# trunsmeetur.net
KiCad netlist of a schematic drawn in EAGLE
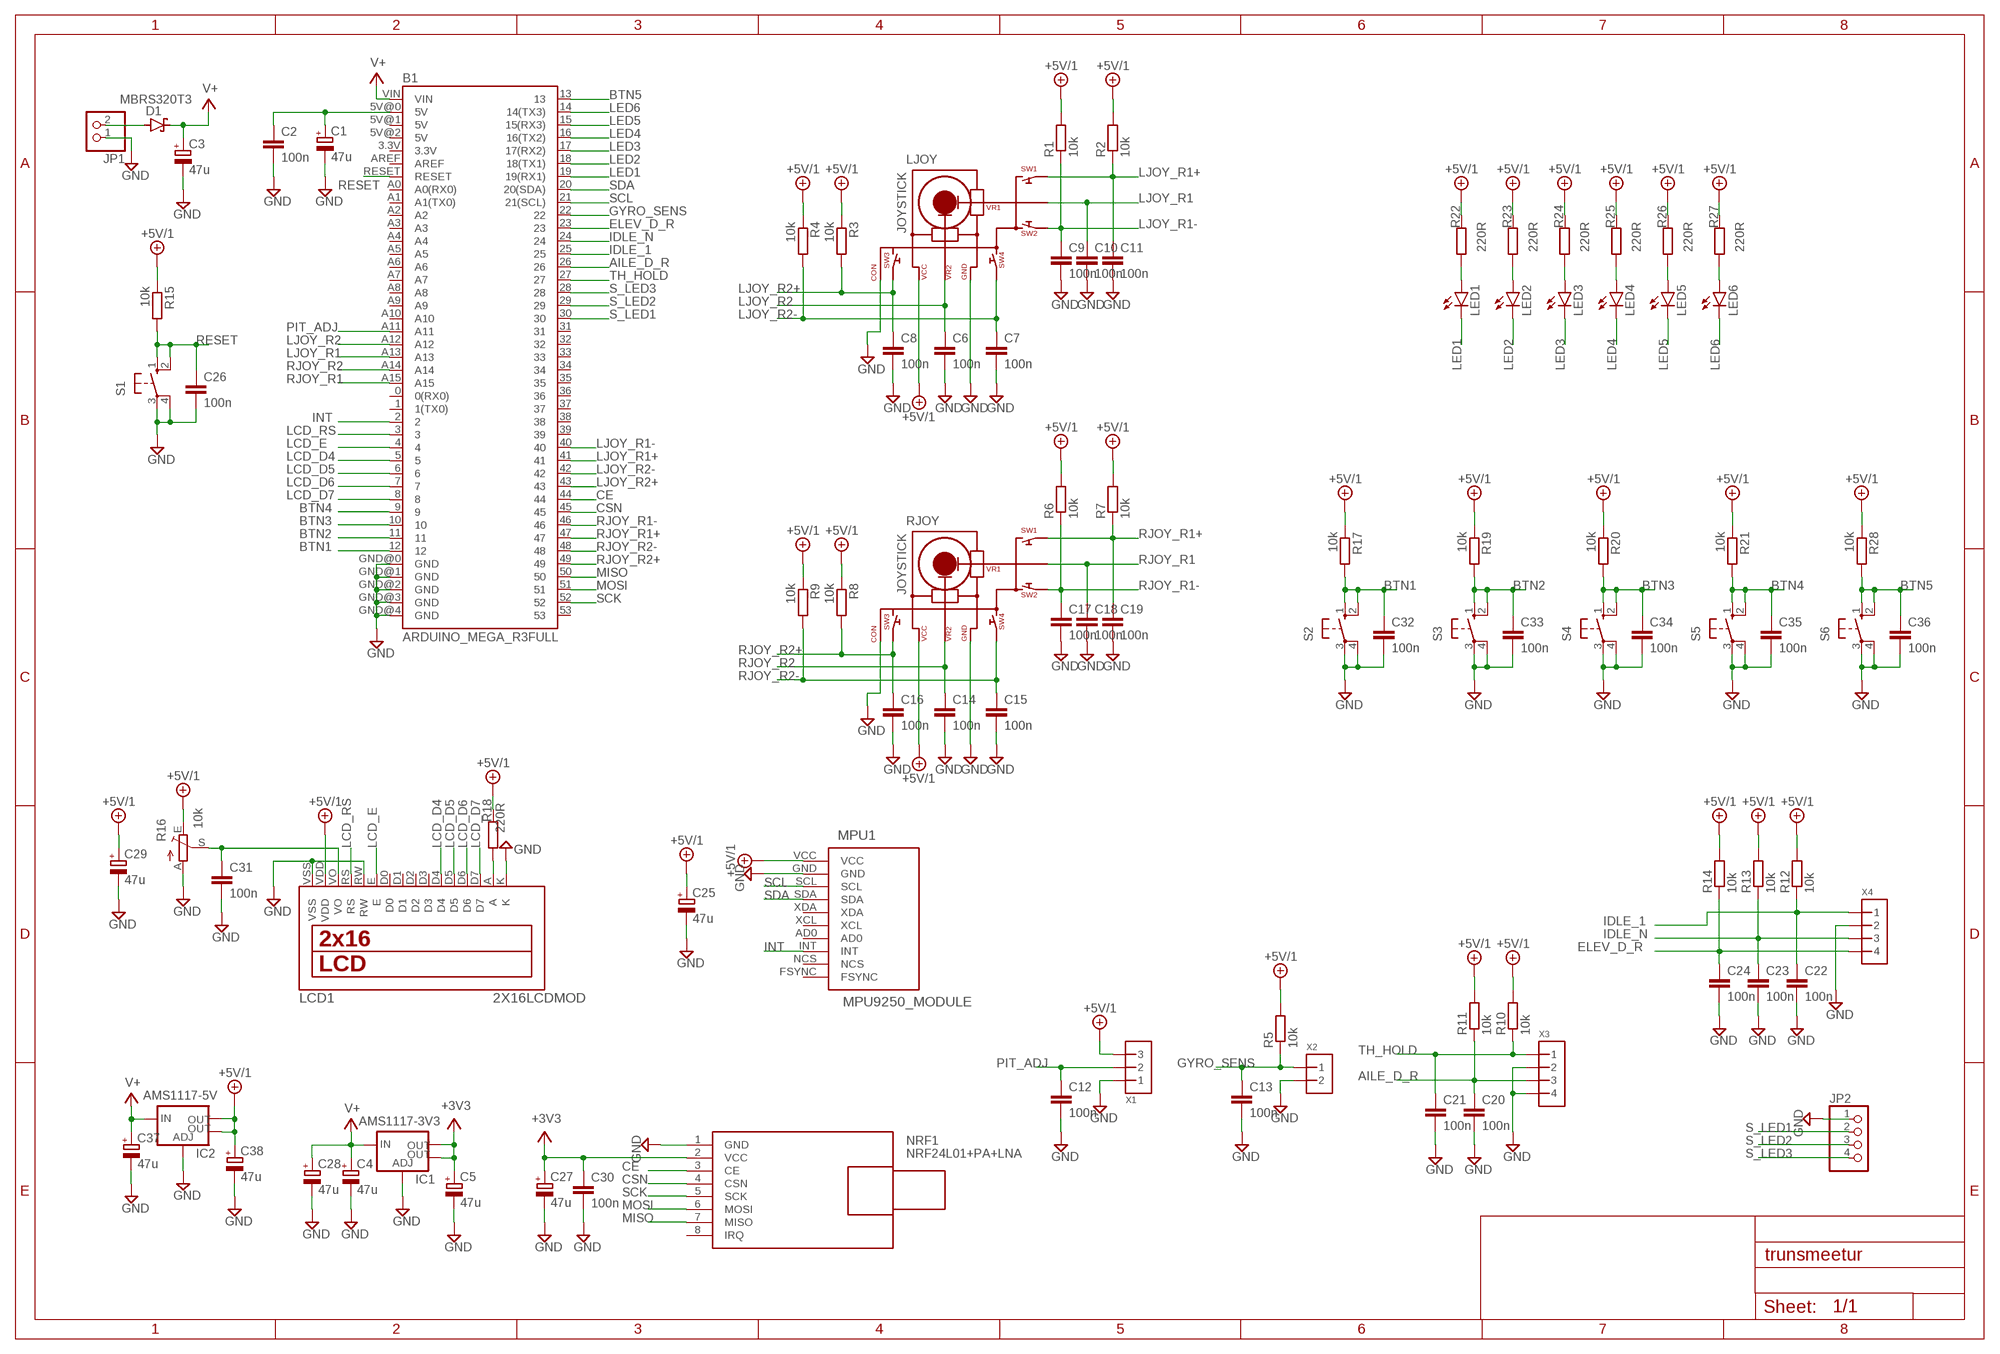
[diagram p0: schematic, sheet 1]

(export (version "E")
  (design (tool "Eeschema 10.0.6"))
  (components
    (comp (ref "B1")
      (value "ARDUINO_MEGA_R3FULL")
      (footprint "eagle-import:ARDUINO_MEGA")
      (libsource (lib "eagle-import") (part "ARDUINO_MEGA_R3FULL"))
    )
    (comp (ref "C1")
      (value "47u")
      (footprint "eagle-import:153CLV-0605")
      (libsource (lib "eagle-import") (part "CPOL-EU153CLV-0605"))
    )
    (comp (ref "C2")
      (value "100n")
      (footprint "eagle-import:C0805")
      (libsource (lib "eagle-import") (part "C-EUC0805"))
    )
    (comp (ref "C3")
      (value "47u")
      (footprint "eagle-import:153CLV-0605")
      (libsource (lib "eagle-import") (part "CPOL-EU153CLV-0605"))
    )
    (comp (ref "C4")
      (value "47u")
      (footprint "eagle-import:153CLV-0605")
      (libsource (lib "eagle-import") (part "CPOL-EU153CLV-0605"))
    )
    (comp (ref "C5")
      (value "47u")
      (footprint "eagle-import:153CLV-0605")
      (libsource (lib "eagle-import") (part "CPOL-EU153CLV-0605"))
    )
    (comp (ref "C6")
      (value "100n")
      (footprint "eagle-import:C0805")
      (libsource (lib "eagle-import") (part "C-EUC0805"))
    )
    (comp (ref "C7")
      (value "100n")
      (footprint "eagle-import:C0805")
      (libsource (lib "eagle-import") (part "C-EUC0805"))
    )
    (comp (ref "C8")
      (value "100n")
      (footprint "eagle-import:C0805")
      (libsource (lib "eagle-import") (part "C-EUC0805"))
    )
    (comp (ref "C9")
      (value "100n")
      (footprint "eagle-import:C0805")
      (libsource (lib "eagle-import") (part "C-EUC0805"))
    )
    (comp (ref "C10")
      (value "100n")
      (footprint "eagle-import:C0805")
      (libsource (lib "eagle-import") (part "C-EUC0805"))
    )
    (comp (ref "C11")
      (value "100n")
      (footprint "eagle-import:C0805")
      (libsource (lib "eagle-import") (part "C-EUC0805"))
    )
    (comp (ref "C12")
      (value "100n")
      (footprint "eagle-import:C0805")
      (libsource (lib "eagle-import") (part "C-EUC0805"))
    )
    (comp (ref "C13")
      (value "100n")
      (footprint "eagle-import:C0805")
      (libsource (lib "eagle-import") (part "C-EUC0805"))
    )
    (comp (ref "C14")
      (value "100n")
      (footprint "eagle-import:C0805")
      (libsource (lib "eagle-import") (part "C-EUC0805"))
    )
    (comp (ref "C15")
      (value "100n")
      (footprint "eagle-import:C0805")
      (libsource (lib "eagle-import") (part "C-EUC0805"))
    )
    (comp (ref "C16")
      (value "100n")
      (footprint "eagle-import:C0805")
      (libsource (lib "eagle-import") (part "C-EUC0805"))
    )
    (comp (ref "C17")
      (value "100n")
      (footprint "eagle-import:C0805")
      (libsource (lib "eagle-import") (part "C-EUC0805"))
    )
    (comp (ref "C18")
      (value "100n")
      (footprint "eagle-import:C0805")
      (libsource (lib "eagle-import") (part "C-EUC0805"))
    )
    (comp (ref "C19")
      (value "100n")
      (footprint "eagle-import:C0805")
      (libsource (lib "eagle-import") (part "C-EUC0805"))
    )
    (comp (ref "C20")
      (value "100n")
      (footprint "eagle-import:C0805")
      (libsource (lib "eagle-import") (part "C-EUC0805"))
    )
    (comp (ref "C21")
      (value "100n")
      (footprint "eagle-import:C0805")
      (libsource (lib "eagle-import") (part "C-EUC0805"))
    )
    (comp (ref "C22")
      (value "100n")
      (footprint "eagle-import:C0805")
      (libsource (lib "eagle-import") (part "C-EUC0805"))
    )
    (comp (ref "C23")
      (value "100n")
      (footprint "eagle-import:C0805")
      (libsource (lib "eagle-import") (part "C-EUC0805"))
    )
    (comp (ref "C24")
      (value "100n")
      (footprint "eagle-import:C0805")
      (libsource (lib "eagle-import") (part "C-EUC0805"))
    )
    (comp (ref "C25")
      (value "47u")
      (footprint "eagle-import:153CLV-0605")
      (libsource (lib "eagle-import") (part "CPOL-EU153CLV-0605"))
    )
    (comp (ref "C26")
      (value "100n")
      (footprint "eagle-import:C0805")
      (libsource (lib "eagle-import") (part "C-EUC0805"))
    )
    (comp (ref "C27")
      (value "47u")
      (footprint "eagle-import:153CLV-0605")
      (libsource (lib "eagle-import") (part "CPOL-EU153CLV-0605"))
    )
    (comp (ref "C28")
      (value "47u")
      (footprint "eagle-import:153CLV-0605")
      (libsource (lib "eagle-import") (part "CPOL-EU153CLV-0605"))
    )
    (comp (ref "C29")
      (value "47u")
      (footprint "eagle-import:153CLV-0605")
      (libsource (lib "eagle-import") (part "CPOL-EU153CLV-0605"))
    )
    (comp (ref "C30")
      (value "100n")
      (footprint "eagle-import:C0805")
      (libsource (lib "eagle-import") (part "C-EUC0805"))
    )
    (comp (ref "C31")
      (value "100n")
      (footprint "eagle-import:C0805")
      (libsource (lib "eagle-import") (part "C-EUC0805"))
    )
    (comp (ref "C32")
      (value "100n")
      (footprint "eagle-import:C0805")
      (libsource (lib "eagle-import") (part "C-EUC0805"))
    )
    (comp (ref "C33")
      (value "100n")
      (footprint "eagle-import:C0805")
      (libsource (lib "eagle-import") (part "C-EUC0805"))
    )
    (comp (ref "C34")
      (value "100n")
      (footprint "eagle-import:C0805")
      (libsource (lib "eagle-import") (part "C-EUC0805"))
    )
    (comp (ref "C35")
      (value "100n")
      (footprint "eagle-import:C0805")
      (libsource (lib "eagle-import") (part "C-EUC0805"))
    )
    (comp (ref "C36")
      (value "100n")
      (footprint "eagle-import:C0805")
      (libsource (lib "eagle-import") (part "C-EUC0805"))
    )
    (comp (ref "C37")
      (value "47u")
      (footprint "eagle-import:153CLV-0605")
      (libsource (lib "eagle-import") (part "CPOL-EU153CLV-0605"))
    )
    (comp (ref "C38")
      (value "47u")
      (footprint "eagle-import:153CLV-0605")
      (libsource (lib "eagle-import") (part "CPOL-EU153CLV-0605"))
    )
    (comp (ref "D1")
      (value "MBRS320T3")
      (footprint "eagle-import:SMC")
      (libsource (lib "eagle-import") (part "MBRS30T32"))
    )
    (comp (ref "IC1")
      (value "AMS1117-3V3")
      (footprint "eagle-import:SOT223")
      (libsource (lib "eagle-import") (part "V_REG_LM1117SOT223"))
    )
    (comp (ref "IC2")
      (value "AMS1117-5V")
      (footprint "eagle-import:SOT223")
      (libsource (lib "eagle-import") (part "V_REG_LM1117SOT223"))
    )
    (comp (ref "JP1")
      (value "PINHD-1X2")
      (footprint "eagle-import:1X02")
      (libsource (lib "eagle-import") (part "PINHD-1X2"))
    )
    (comp (ref "JP2")
      (value "PINHD-1X4")
      (footprint "eagle-import:1X04")
      (libsource (lib "eagle-import") (part "PINHD-1X4"))
    )
    (comp (ref "LCD1")
      (value "2X16LCDMOD")
      (footprint "eagle-import:LCD16X2MOD")
      (libsource (lib "eagle-import") (part "2X16LCDMOD"))
    )
    (comp (ref "LED1")
      (value "LEDCHIPLED_0805")
      (footprint "eagle-import:CHIPLED_0805")
      (libsource (lib "eagle-import") (part "LEDCHIPLED_0805"))
    )
    (comp (ref "LED2")
      (value "LEDCHIPLED_0805")
      (footprint "eagle-import:CHIPLED_0805")
      (libsource (lib "eagle-import") (part "LEDCHIPLED_0805"))
    )
    (comp (ref "LED3")
      (value "LEDCHIPLED_0805")
      (footprint "eagle-import:CHIPLED_0805")
      (libsource (lib "eagle-import") (part "LEDCHIPLED_0805"))
    )
    (comp (ref "LED4")
      (value "LEDCHIPLED_0805")
      (footprint "eagle-import:CHIPLED_0805")
      (libsource (lib "eagle-import") (part "LEDCHIPLED_0805"))
    )
    (comp (ref "LED5")
      (value "LEDCHIPLED_0805")
      (footprint "eagle-import:CHIPLED_0805")
      (libsource (lib "eagle-import") (part "LEDCHIPLED_0805"))
    )
    (comp (ref "LED6")
      (value "LEDCHIPLED_0805")
      (footprint "eagle-import:CHIPLED_0805")
      (libsource (lib "eagle-import") (part "LEDCHIPLED_0805"))
    )
    (comp (ref "LJOY")
      (value "JOYSTICK")
      (footprint "eagle-import:JOYSTICKCONNECTOR")
      (libsource (lib "eagle-import") (part "JOYSTICK"))
    )
    (comp (ref "MPU1")
      (value "MPU9250_MODULE")
      (footprint "eagle-import:MPU9250_MODULE")
      (libsource (lib "eagle-import") (part "MPU9250_MODULE"))
    )
    (comp (ref "NRF1")
      (value "NRF24L01+PA+LNA")
      (footprint "eagle-import:WIRELESS-NRF24L01-PA-EXT")
      (libsource (lib "eagle-import") (part "WIRELESS-NRF24L01-PA-EXT"))
    )
    (comp (ref "R1")
      (value "10k")
      (footprint "eagle-import:M0805")
      (libsource (lib "eagle-import") (part "R-EU_M0805"))
    )
    (comp (ref "R2")
      (value "10k")
      (footprint "eagle-import:M0805")
      (libsource (lib "eagle-import") (part "R-EU_M0805"))
    )
    (comp (ref "R3")
      (value "10k")
      (footprint "eagle-import:M0805")
      (libsource (lib "eagle-import") (part "R-EU_M0805"))
    )
    (comp (ref "R4")
      (value "10k")
      (footprint "eagle-import:M0805")
      (libsource (lib "eagle-import") (part "R-EU_M0805"))
    )
    (comp (ref "R5")
      (value "10k")
      (footprint "eagle-import:M0805")
      (libsource (lib "eagle-import") (part "R-EU_M0805"))
    )
    (comp (ref "R6")
      (value "10k")
      (footprint "eagle-import:M0805")
      (libsource (lib "eagle-import") (part "R-EU_M0805"))
    )
    (comp (ref "R7")
      (value "10k")
      (footprint "eagle-import:M0805")
      (libsource (lib "eagle-import") (part "R-EU_M0805"))
    )
    (comp (ref "R8")
      (value "10k")
      (footprint "eagle-import:M0805")
      (libsource (lib "eagle-import") (part "R-EU_M0805"))
    )
    (comp (ref "R9")
      (value "10k")
      (footprint "eagle-import:M0805")
      (libsource (lib "eagle-import") (part "R-EU_M0805"))
    )
    (comp (ref "R10")
      (value "10k")
      (footprint "eagle-import:M0805")
      (libsource (lib "eagle-import") (part "R-EU_M0805"))
    )
    (comp (ref "R11")
      (value "10k")
      (footprint "eagle-import:M0805")
      (libsource (lib "eagle-import") (part "R-EU_M0805"))
    )
    (comp (ref "R12")
      (value "10k")
      (footprint "eagle-import:M0805")
      (libsource (lib "eagle-import") (part "R-EU_M0805"))
    )
    (comp (ref "R13")
      (value "10k")
      (footprint "eagle-import:M0805")
      (libsource (lib "eagle-import") (part "R-EU_M0805"))
    )
    (comp (ref "R14")
      (value "10k")
      (footprint "eagle-import:M0805")
      (libsource (lib "eagle-import") (part "R-EU_M0805"))
    )
    (comp (ref "R15")
      (value "10k")
      (footprint "eagle-import:M0805")
      (libsource (lib "eagle-import") (part "R-EU_M0805"))
    )
    (comp (ref "R16")
      (value "10k")
      (footprint "eagle-import:CA9V")
      (libsource (lib "eagle-import") (part "TRIM_EU-CA9V"))
    )
    (comp (ref "R17")
      (value "10k")
      (footprint "eagle-import:M0805")
      (libsource (lib "eagle-import") (part "R-EU_M0805"))
    )
    (comp (ref "R18")
      (value "220R")
      (footprint "eagle-import:M0805")
      (libsource (lib "eagle-import") (part "R-EU_M0805"))
    )
    (comp (ref "R19")
      (value "10k")
      (footprint "eagle-import:M0805")
      (libsource (lib "eagle-import") (part "R-EU_M0805"))
    )
    (comp (ref "R20")
      (value "10k")
      (footprint "eagle-import:M0805")
      (libsource (lib "eagle-import") (part "R-EU_M0805"))
    )
    (comp (ref "R21")
      (value "10k")
      (footprint "eagle-import:M0805")
      (libsource (lib "eagle-import") (part "R-EU_M0805"))
    )
    (comp (ref "R22")
      (value "220R")
      (footprint "eagle-import:M0805")
      (libsource (lib "eagle-import") (part "R-EU_M0805"))
    )
    (comp (ref "R23")
      (value "220R")
      (footprint "eagle-import:M0805")
      (libsource (lib "eagle-import") (part "R-EU_M0805"))
    )
    (comp (ref "R24")
      (value "220R")
      (footprint "eagle-import:M0805")
      (libsource (lib "eagle-import") (part "R-EU_M0805"))
    )
    (comp (ref "R25")
      (value "220R")
      (footprint "eagle-import:M0805")
      (libsource (lib "eagle-import") (part "R-EU_M0805"))
    )
    (comp (ref "R26")
      (value "220R")
      (footprint "eagle-import:M0805")
      (libsource (lib "eagle-import") (part "R-EU_M0805"))
    )
    (comp (ref "R27")
      (value "220R")
      (footprint "eagle-import:M0805")
      (libsource (lib "eagle-import") (part "R-EU_M0805"))
    )
    (comp (ref "R28")
      (value "10k")
      (footprint "eagle-import:M0805")
      (libsource (lib "eagle-import") (part "R-EU_M0805"))
    )
    (comp (ref "RJOY")
      (value "JOYSTICK")
      (footprint "eagle-import:JOYSTICKCONNECTOR")
      (libsource (lib "eagle-import") (part "JOYSTICK"))
    )
    (comp (ref "S1")
      (value "10-XX")
      (footprint "eagle-import:B3F-10XX")
      (fields (field (name "MPN") "B3F-1000"))
      (libsource (lib "eagle-import") (part "10-XX"))
    )
    (comp (ref "S2")
      (value "10-XX")
      (footprint "eagle-import:B3F-10XX")
      (fields (field (name "MPN") "B3F-1000"))
      (libsource (lib "eagle-import") (part "10-XX"))
    )
    (comp (ref "S3")
      (value "10-XX")
      (footprint "eagle-import:B3F-10XX")
      (fields (field (name "MPN") "B3F-1000"))
      (libsource (lib "eagle-import") (part "10-XX"))
    )
    (comp (ref "S4")
      (value "10-XX")
      (footprint "eagle-import:B3F-10XX")
      (fields (field (name "MPN") "B3F-1000"))
      (libsource (lib "eagle-import") (part "10-XX"))
    )
    (comp (ref "S5")
      (value "10-XX")
      (footprint "eagle-import:B3F-10XX")
      (fields (field (name "MPN") "B3F-1000"))
      (libsource (lib "eagle-import") (part "10-XX"))
    )
    (comp (ref "S6")
      (value "10-XX")
      (footprint "eagle-import:B3F-10XX")
      (fields (field (name "MPN") "B3F-1000"))
      (libsource (lib "eagle-import") (part "10-XX"))
    )
    (comp (ref "X1")
      (value "3PIN")
      (footprint "eagle-import:3PINCONNECTOR")
      (libsource (lib "eagle-import") (part "3PIN"))
    )
    (comp (ref "X2")
      (value "2PIN")
      (footprint "eagle-import:2PINCONNECTOR")
      (libsource (lib "eagle-import") (part "2PIN"))
    )
    (comp (ref "X3")
      (value "4PIN")
      (footprint "eagle-import:4PINCONNECTOR")
      (libsource (lib "eagle-import") (part "4PIN"))
    )
    (comp (ref "X4")
      (value "4PIN")
      (footprint "eagle-import:4PINCONNECTOR")
      (libsource (lib "eagle-import") (part "4PIN"))
    )
  )
  (nets
    (net (code "1") (name "+3V3") (class "Default")
      (node (ref "C27") (pin "+") (pinfunction "+_+") (pintype "passive"))
      (node (ref "C30") (pin "1") (pinfunction "1_1") (pintype "passive"))
      (node (ref "C5") (pin "+") (pinfunction "+_+") (pintype "passive"))
      (node (ref "IC1") (pin "2") (pinfunction "OUT_2") (pintype "output"))
      (node (ref "IC1") (pin "4") (pinfunction "OUT_4") (pintype "output"))
      (node (ref "NRF1") (pin "2") (pinfunction "VCC_2") (pintype "power_in"))
    )
    (net (code "2") (name "+5V{slash}1") (class "Default")
      (node (ref "C25") (pin "+") (pinfunction "+_+") (pintype "passive"))
      (node (ref "C29") (pin "+") (pinfunction "+_+") (pintype "passive"))
      (node (ref "C38") (pin "+") (pinfunction "+_+") (pintype "passive"))
      (node (ref "IC2") (pin "2") (pinfunction "OUT_2") (pintype "output"))
      (node (ref "IC2") (pin "4") (pinfunction "OUT_4") (pintype "output"))
      (node (ref "LCD1") (pin "VDD") (pinfunction "VDD_VDD") (pintype "bidirectional"))
      (node (ref "LJOY") (pin "VCC") (pinfunction "VCC_VCC") (pintype "bidirectional"))
      (node (ref "MPU1") (pin "VCC") (pinfunction "VCC_VCC") (pintype "bidirectional"))
      (node (ref "R1") (pin "2") (pinfunction "2_2") (pintype "passive"))
      (node (ref "R10") (pin "2") (pinfunction "2_2") (pintype "passive"))
      (node (ref "R11") (pin "2") (pinfunction "2_2") (pintype "passive"))
      (node (ref "R12") (pin "2") (pinfunction "2_2") (pintype "passive"))
      (node (ref "R13") (pin "2") (pinfunction "2_2") (pintype "passive"))
      (node (ref "R14") (pin "2") (pinfunction "2_2") (pintype "passive"))
      (node (ref "R15") (pin "1") (pinfunction "1_1") (pintype "passive"))
      (node (ref "R16") (pin "E") (pinfunction "E_E") (pintype "passive"))
      (node (ref "R17") (pin "1") (pinfunction "1_1") (pintype "passive"))
      (node (ref "R18") (pin "1") (pinfunction "1_1") (pintype "passive"))
      (node (ref "R19") (pin "1") (pinfunction "1_1") (pintype "passive"))
      (node (ref "R2") (pin "2") (pinfunction "2_2") (pintype "passive"))
      (node (ref "R20") (pin "1") (pinfunction "1_1") (pintype "passive"))
      (node (ref "R21") (pin "1") (pinfunction "1_1") (pintype "passive"))
      (node (ref "R22") (pin "1") (pinfunction "1_1") (pintype "passive"))
      (node (ref "R23") (pin "1") (pinfunction "1_1") (pintype "passive"))
      (node (ref "R24") (pin "1") (pinfunction "1_1") (pintype "passive"))
      (node (ref "R25") (pin "1") (pinfunction "1_1") (pintype "passive"))
      (node (ref "R26") (pin "1") (pinfunction "1_1") (pintype "passive"))
      (node (ref "R27") (pin "1") (pinfunction "1_1") (pintype "passive"))
      (node (ref "R28") (pin "1") (pinfunction "1_1") (pintype "passive"))
      (node (ref "R3") (pin "1") (pinfunction "1_1") (pintype "passive"))
      (node (ref "R4") (pin "1") (pinfunction "1_1") (pintype "passive"))
      (node (ref "R5") (pin "2") (pinfunction "2_2") (pintype "passive"))
      (node (ref "R6") (pin "2") (pinfunction "2_2") (pintype "passive"))
      (node (ref "R7") (pin "2") (pinfunction "2_2") (pintype "passive"))
      (node (ref "R8") (pin "1") (pinfunction "1_1") (pintype "passive"))
      (node (ref "R9") (pin "1") (pinfunction "1_1") (pintype "passive"))
      (node (ref "RJOY") (pin "VCC") (pinfunction "VCC_VCC") (pintype "bidirectional"))
      (node (ref "X1") (pin "3") (pinfunction "3_3") (pintype "bidirectional"))
    )
    (net (code "3") (name "/AILE_D_R") (class "Default")
      (node (ref "B1") (pin "26") (pinfunction "26_26") (pintype "bidirectional"))
      (node (ref "C20") (pin "1") (pinfunction "1_1") (pintype "passive"))
      (node (ref "R11") (pin "1") (pinfunction "1_1") (pintype "passive"))
      (node (ref "X3") (pin "3") (pinfunction "3_3") (pintype "bidirectional"))
    )
    (net (code "4") (name "/BTN1") (class "Default")
      (node (ref "B1") (pin "12") (pinfunction "12_12") (pintype "bidirectional"))
      (node (ref "C32") (pin "1") (pinfunction "1_1") (pintype "passive"))
      (node (ref "R17") (pin "2") (pinfunction "2_2") (pintype "passive"))
      (node (ref "S2") (pin "1") (pinfunction "S_1") (pintype "passive"))
      (node (ref "S2") (pin "2") (pinfunction "S1_2") (pintype "passive"))
    )
    (net (code "5") (name "/BTN2") (class "Default")
      (node (ref "B1") (pin "11") (pinfunction "11_11") (pintype "bidirectional"))
      (node (ref "C33") (pin "1") (pinfunction "1_1") (pintype "passive"))
      (node (ref "R19") (pin "2") (pinfunction "2_2") (pintype "passive"))
      (node (ref "S3") (pin "1") (pinfunction "S_1") (pintype "passive"))
      (node (ref "S3") (pin "2") (pinfunction "S1_2") (pintype "passive"))
    )
    (net (code "6") (name "/BTN3") (class "Default")
      (node (ref "B1") (pin "10") (pinfunction "10_10") (pintype "bidirectional"))
      (node (ref "C34") (pin "1") (pinfunction "1_1") (pintype "passive"))
      (node (ref "R20") (pin "2") (pinfunction "2_2") (pintype "passive"))
      (node (ref "S4") (pin "1") (pinfunction "S_1") (pintype "passive"))
      (node (ref "S4") (pin "2") (pinfunction "S1_2") (pintype "passive"))
    )
    (net (code "7") (name "/BTN4") (class "Default")
      (node (ref "B1") (pin "9") (pinfunction "9_9") (pintype "bidirectional"))
      (node (ref "C35") (pin "1") (pinfunction "1_1") (pintype "passive"))
      (node (ref "R21") (pin "2") (pinfunction "2_2") (pintype "passive"))
      (node (ref "S5") (pin "1") (pinfunction "S_1") (pintype "passive"))
      (node (ref "S5") (pin "2") (pinfunction "S1_2") (pintype "passive"))
    )
    (net (code "8") (name "/BTN5") (class "Default")
      (node (ref "B1") (pin "13") (pinfunction "13_13") (pintype "bidirectional"))
      (node (ref "C36") (pin "1") (pinfunction "1_1") (pintype "passive"))
      (node (ref "R28") (pin "2") (pinfunction "2_2") (pintype "passive"))
      (node (ref "S6") (pin "1") (pinfunction "S_1") (pintype "passive"))
      (node (ref "S6") (pin "2") (pinfunction "S1_2") (pintype "passive"))
    )
    (net (code "9") (name "/CE") (class "Default")
      (node (ref "B1") (pin "44") (pinfunction "44_44") (pintype "bidirectional"))
      (node (ref "NRF1") (pin "3") (pinfunction "CE_3") (pintype "bidirectional"))
    )
    (net (code "10") (name "/CSN") (class "Default")
      (node (ref "B1") (pin "45") (pinfunction "45_45") (pintype "bidirectional"))
      (node (ref "NRF1") (pin "4") (pinfunction "CSN_4") (pintype "bidirectional"))
    )
    (net (code "11") (name "/ELEV_D_R") (class "Default")
      (node (ref "B1") (pin "23") (pinfunction "23_23") (pintype "bidirectional"))
      (node (ref "C24") (pin "1") (pinfunction "1_1") (pintype "passive"))
      (node (ref "R14") (pin "1") (pinfunction "1_1") (pintype "passive"))
      (node (ref "X4") (pin "4") (pinfunction "4_4") (pintype "bidirectional"))
    )
    (net (code "12") (name "/GYRO_SENS") (class "Default")
      (node (ref "B1") (pin "22") (pinfunction "22_22") (pintype "bidirectional"))
      (node (ref "C13") (pin "1") (pinfunction "1_1") (pintype "passive"))
      (node (ref "R5") (pin "1") (pinfunction "1_1") (pintype "passive"))
      (node (ref "X2") (pin "1") (pinfunction "1_1") (pintype "bidirectional"))
    )
    (net (code "13") (name "/IDLE_1") (class "Default")
      (node (ref "B1") (pin "25") (pinfunction "25_25") (pintype "bidirectional"))
      (node (ref "C22") (pin "1") (pinfunction "1_1") (pintype "passive"))
      (node (ref "R12") (pin "1") (pinfunction "1_1") (pintype "passive"))
      (node (ref "X4") (pin "1") (pinfunction "1_1") (pintype "bidirectional"))
    )
    (net (code "14") (name "/IDLE_N") (class "Default")
      (node (ref "B1") (pin "24") (pinfunction "24_24") (pintype "bidirectional"))
      (node (ref "C23") (pin "1") (pinfunction "1_1") (pintype "passive"))
      (node (ref "R13") (pin "1") (pinfunction "1_1") (pintype "passive"))
      (node (ref "X4") (pin "3") (pinfunction "3_3") (pintype "bidirectional"))
    )
    (net (code "15") (name "/INT") (class "Default")
      (node (ref "B1") (pin "2") (pinfunction "2_2") (pintype "bidirectional"))
      (node (ref "MPU1") (pin "INT") (pinfunction "INT_INT") (pintype "bidirectional"))
    )
    (net (code "16") (name "/LCD_D4") (class "Default")
      (node (ref "B1") (pin "5") (pinfunction "5_5") (pintype "bidirectional"))
      (node (ref "LCD1") (pin "D4") (pinfunction "D4_D4") (pintype "bidirectional"))
    )
    (net (code "17") (name "/LCD_D5") (class "Default")
      (node (ref "B1") (pin "6") (pinfunction "6_6") (pintype "bidirectional"))
      (node (ref "LCD1") (pin "D5") (pinfunction "D5_D5") (pintype "bidirectional"))
    )
    (net (code "18") (name "/LCD_D6") (class "Default")
      (node (ref "B1") (pin "7") (pinfunction "7_7") (pintype "bidirectional"))
      (node (ref "LCD1") (pin "D6") (pinfunction "D6_D6") (pintype "bidirectional"))
    )
    (net (code "19") (name "/LCD_D7") (class "Default")
      (node (ref "B1") (pin "8") (pinfunction "8_8") (pintype "bidirectional"))
      (node (ref "LCD1") (pin "D7") (pinfunction "D7_D7") (pintype "bidirectional"))
    )
    (net (code "20") (name "/LCD_E") (class "Default")
      (node (ref "B1") (pin "4") (pinfunction "4_4") (pintype "bidirectional"))
      (node (ref "LCD1") (pin "E") (pinfunction "E_E") (pintype "bidirectional"))
    )
    (net (code "21") (name "/LCD_RS") (class "Default")
      (node (ref "B1") (pin "3") (pinfunction "3_3") (pintype "bidirectional"))
      (node (ref "LCD1") (pin "RS") (pinfunction "RS_RS") (pintype "bidirectional"))
    )
    (net (code "22") (name "/LED1") (class "Default")
      (node (ref "B1") (pin "19") (pinfunction "19(RX1)_19") (pintype "bidirectional"))
      (node (ref "LED1") (pin "C") (pinfunction "C_C") (pintype "passive"))
    )
    (net (code "23") (name "/LED2") (class "Default")
      (node (ref "B1") (pin "18") (pinfunction "18(TX1)_18") (pintype "bidirectional"))
      (node (ref "LED2") (pin "C") (pinfunction "C_C") (pintype "passive"))
    )
    (net (code "24") (name "/LED3") (class "Default")
      (node (ref "B1") (pin "17") (pinfunction "17(RX2)_17") (pintype "bidirectional"))
      (node (ref "LED3") (pin "C") (pinfunction "C_C") (pintype "passive"))
    )
    (net (code "25") (name "/LED4") (class "Default")
      (node (ref "B1") (pin "16") (pinfunction "16(TX2)_16") (pintype "bidirectional"))
      (node (ref "LED4") (pin "C") (pinfunction "C_C") (pintype "passive"))
    )
    (net (code "26") (name "/LED5") (class "Default")
      (node (ref "B1") (pin "15") (pinfunction "15(RX3)_15") (pintype "bidirectional"))
      (node (ref "LED5") (pin "C") (pinfunction "C_C") (pintype "passive"))
    )
    (net (code "27") (name "/LED6") (class "Default")
      (node (ref "B1") (pin "14") (pinfunction "14(TX3)_14") (pintype "bidirectional"))
      (node (ref "LED6") (pin "C") (pinfunction "C_C") (pintype "passive"))
    )
    (net (code "28") (name "/LJOY_R1") (class "Default")
      (node (ref "B1") (pin "A13") (pinfunction "A13_A13") (pintype "bidirectional"))
      (node (ref "C10") (pin "1") (pinfunction "1_1") (pintype "passive"))
      (node (ref "LJOY") (pin "VR1") (pinfunction "VR1_VR1") (pintype "bidirectional"))
    )
    (net (code "29") (name "/LJOY_R1+") (class "Default")
      (node (ref "B1") (pin "41") (pinfunction "41_41") (pintype "bidirectional"))
      (node (ref "C11") (pin "1") (pinfunction "1_1") (pintype "passive"))
      (node (ref "LJOY") (pin "SW1") (pinfunction "SW1_SW1") (pintype "bidirectional"))
      (node (ref "R2") (pin "1") (pinfunction "1_1") (pintype "passive"))
    )
    (net (code "30") (name "/LJOY_R1-") (class "Default")
      (node (ref "B1") (pin "40") (pinfunction "40_40") (pintype "bidirectional"))
      (node (ref "C9") (pin "1") (pinfunction "1_1") (pintype "passive"))
      (node (ref "LJOY") (pin "SW2") (pinfunction "SW2_SW2") (pintype "bidirectional"))
      (node (ref "R1") (pin "1") (pinfunction "1_1") (pintype "passive"))
    )
    (net (code "31") (name "/LJOY_R2") (class "Default")
      (node (ref "B1") (pin "A12") (pinfunction "A12_A12") (pintype "bidirectional"))
      (node (ref "C6") (pin "1") (pinfunction "1_1") (pintype "passive"))
      (node (ref "LJOY") (pin "VR2") (pinfunction "VR2_VR2") (pintype "bidirectional"))
    )
    (net (code "32") (name "/LJOY_R2+") (class "Default")
      (node (ref "B1") (pin "43") (pinfunction "43_43") (pintype "bidirectional"))
      (node (ref "C8") (pin "1") (pinfunction "1_1") (pintype "passive"))
      (node (ref "LJOY") (pin "SW3") (pinfunction "SW3_SW3") (pintype "bidirectional"))
      (node (ref "R3") (pin "2") (pinfunction "2_2") (pintype "passive"))
    )
    (net (code "33") (name "/LJOY_R2-") (class "Default")
      (node (ref "B1") (pin "42") (pinfunction "42_42") (pintype "bidirectional"))
      (node (ref "C7") (pin "1") (pinfunction "1_1") (pintype "passive"))
      (node (ref "LJOY") (pin "SW4") (pinfunction "SW4_SW4") (pintype "bidirectional"))
      (node (ref "R4") (pin "2") (pinfunction "2_2") (pintype "passive"))
    )
    (net (code "34") (name "/MISO") (class "Default")
      (node (ref "B1") (pin "50") (pinfunction "50_50") (pintype "bidirectional"))
      (node (ref "NRF1") (pin "7") (pinfunction "MISO_7") (pintype "bidirectional"))
    )
    (net (code "35") (name "/MOSI") (class "Default")
      (node (ref "B1") (pin "51") (pinfunction "51_51") (pintype "bidirectional"))
      (node (ref "NRF1") (pin "6") (pinfunction "MOSI_6") (pintype "bidirectional"))
    )
    (net (code "36") (name "/PIT_ADJ") (class "Default")
      (node (ref "B1") (pin "A11") (pinfunction "A11_A11") (pintype "bidirectional"))
      (node (ref "C12") (pin "1") (pinfunction "1_1") (pintype "passive"))
      (node (ref "X1") (pin "2") (pinfunction "2_2") (pintype "bidirectional"))
    )
    (net (code "37") (name "/RESET") (class "Default")
      (node (ref "B1") (pin "RESET") (pinfunction "RESET_RESET") (pintype "bidirectional"))
      (node (ref "C26") (pin "1") (pinfunction "1_1") (pintype "passive"))
      (node (ref "R15") (pin "2") (pinfunction "2_2") (pintype "passive"))
      (node (ref "S1") (pin "1") (pinfunction "S_1") (pintype "passive"))
      (node (ref "S1") (pin "2") (pinfunction "S1_2") (pintype "passive"))
    )
    (net (code "38") (name "/RJOY_R1") (class "Default")
      (node (ref "B1") (pin "A15") (pinfunction "A15_A15") (pintype "bidirectional"))
      (node (ref "C18") (pin "1") (pinfunction "1_1") (pintype "passive"))
      (node (ref "RJOY") (pin "VR1") (pinfunction "VR1_VR1") (pintype "bidirectional"))
    )
    (net (code "39") (name "/RJOY_R1+") (class "Default")
      (node (ref "B1") (pin "47") (pinfunction "47_47") (pintype "bidirectional"))
      (node (ref "C19") (pin "1") (pinfunction "1_1") (pintype "passive"))
      (node (ref "R7") (pin "1") (pinfunction "1_1") (pintype "passive"))
      (node (ref "RJOY") (pin "SW1") (pinfunction "SW1_SW1") (pintype "bidirectional"))
    )
    (net (code "40") (name "/RJOY_R1-") (class "Default")
      (node (ref "B1") (pin "46") (pinfunction "46_46") (pintype "bidirectional"))
      (node (ref "C17") (pin "1") (pinfunction "1_1") (pintype "passive"))
      (node (ref "R6") (pin "1") (pinfunction "1_1") (pintype "passive"))
      (node (ref "RJOY") (pin "SW2") (pinfunction "SW2_SW2") (pintype "bidirectional"))
    )
    (net (code "41") (name "/RJOY_R2") (class "Default")
      (node (ref "B1") (pin "A14") (pinfunction "A14_A14") (pintype "bidirectional"))
      (node (ref "C14") (pin "1") (pinfunction "1_1") (pintype "passive"))
      (node (ref "RJOY") (pin "VR2") (pinfunction "VR2_VR2") (pintype "bidirectional"))
    )
    (net (code "42") (name "/RJOY_R2+") (class "Default")
      (node (ref "B1") (pin "49") (pinfunction "49_49") (pintype "bidirectional"))
      (node (ref "C16") (pin "1") (pinfunction "1_1") (pintype "passive"))
      (node (ref "R8") (pin "2") (pinfunction "2_2") (pintype "passive"))
      (node (ref "RJOY") (pin "SW3") (pinfunction "SW3_SW3") (pintype "bidirectional"))
    )
    (net (code "43") (name "/RJOY_R2-") (class "Default")
      (node (ref "B1") (pin "48") (pinfunction "48_48") (pintype "bidirectional"))
      (node (ref "C15") (pin "1") (pinfunction "1_1") (pintype "passive"))
      (node (ref "R9") (pin "2") (pinfunction "2_2") (pintype "passive"))
      (node (ref "RJOY") (pin "SW4") (pinfunction "SW4_SW4") (pintype "bidirectional"))
    )
    (net (code "44") (name "/SCK") (class "Default")
      (node (ref "B1") (pin "52") (pinfunction "52_52") (pintype "bidirectional"))
      (node (ref "NRF1") (pin "5") (pinfunction "SCK_5") (pintype "bidirectional"))
    )
    (net (code "45") (name "/SCL") (class "Default")
      (node (ref "B1") (pin "21") (pinfunction "21(SCL)_21") (pintype "bidirectional"))
      (node (ref "MPU1") (pin "SCL") (pinfunction "SCL_SCL") (pintype "bidirectional"))
    )
    (net (code "46") (name "/SDA") (class "Default")
      (node (ref "B1") (pin "20") (pinfunction "20(SDA)_20") (pintype "bidirectional"))
      (node (ref "MPU1") (pin "SDA") (pinfunction "SDA_SDA") (pintype "bidirectional"))
    )
    (net (code "47") (name "/S_LED1") (class "Default")
      (node (ref "B1") (pin "30") (pinfunction "30_30") (pintype "bidirectional"))
      (node (ref "JP2") (pin "2") (pinfunction "2_2") (pintype "passive"))
    )
    (net (code "48") (name "/S_LED2") (class "Default")
      (node (ref "B1") (pin "29") (pinfunction "29_29") (pintype "bidirectional"))
      (node (ref "JP2") (pin "3") (pinfunction "3_3") (pintype "passive"))
    )
    (net (code "49") (name "/S_LED3") (class "Default")
      (node (ref "B1") (pin "28") (pinfunction "28_28") (pintype "bidirectional"))
      (node (ref "JP2") (pin "4") (pinfunction "4_4") (pintype "passive"))
    )
    (net (code "50") (name "/TH_HOLD") (class "Default")
      (node (ref "B1") (pin "27") (pinfunction "27_27") (pintype "bidirectional"))
      (node (ref "C21") (pin "1") (pinfunction "1_1") (pintype "passive"))
      (node (ref "R10") (pin "1") (pinfunction "1_1") (pintype "passive"))
      (node (ref "X3") (pin "1") (pinfunction "1_1") (pintype "bidirectional"))
    )
    (net (code "51") (name "GND") (class "Default")
      (node (ref "B1") (pin "GND@0") (pinfunction "GND_GND@0") (pintype "bidirectional"))
      (node (ref "B1") (pin "GND@1") (pinfunction "GND_GND@1") (pintype "bidirectional"))
      (node (ref "B1") (pin "GND@2") (pinfunction "GND_GND@2") (pintype "bidirectional"))
      (node (ref "B1") (pin "GND@3") (pinfunction "GND_GND@3") (pintype "bidirectional"))
      (node (ref "B1") (pin "GND@4") (pinfunction "GND_GND@4") (pintype "bidirectional"))
      (node (ref "C1") (pin "-") (pinfunction "-_-") (pintype "passive"))
      (node (ref "C10") (pin "2") (pinfunction "2_2") (pintype "passive"))
      (node (ref "C11") (pin "2") (pinfunction "2_2") (pintype "passive"))
      (node (ref "C12") (pin "2") (pinfunction "2_2") (pintype "passive"))
      (node (ref "C13") (pin "2") (pinfunction "2_2") (pintype "passive"))
      (node (ref "C14") (pin "2") (pinfunction "2_2") (pintype "passive"))
      (node (ref "C15") (pin "2") (pinfunction "2_2") (pintype "passive"))
      (node (ref "C16") (pin "2") (pinfunction "2_2") (pintype "passive"))
      (node (ref "C17") (pin "2") (pinfunction "2_2") (pintype "passive"))
      (node (ref "C18") (pin "2") (pinfunction "2_2") (pintype "passive"))
      (node (ref "C19") (pin "2") (pinfunction "2_2") (pintype "passive"))
      (node (ref "C2") (pin "2") (pinfunction "2_2") (pintype "passive"))
      (node (ref "C20") (pin "2") (pinfunction "2_2") (pintype "passive"))
      (node (ref "C21") (pin "2") (pinfunction "2_2") (pintype "passive"))
      (node (ref "C22") (pin "2") (pinfunction "2_2") (pintype "passive"))
      (node (ref "C23") (pin "2") (pinfunction "2_2") (pintype "passive"))
      (node (ref "C24") (pin "2") (pinfunction "2_2") (pintype "passive"))
      (node (ref "C25") (pin "-") (pinfunction "-_-") (pintype "passive"))
      (node (ref "C26") (pin "2") (pinfunction "2_2") (pintype "passive"))
      (node (ref "C27") (pin "-") (pinfunction "-_-") (pintype "passive"))
      (node (ref "C28") (pin "-") (pinfunction "-_-") (pintype "passive"))
      (node (ref "C29") (pin "-") (pinfunction "-_-") (pintype "passive"))
      (node (ref "C3") (pin "-") (pinfunction "-_-") (pintype "passive"))
      (node (ref "C30") (pin "2") (pinfunction "2_2") (pintype "passive"))
      (node (ref "C31") (pin "2") (pinfunction "2_2") (pintype "passive"))
      (node (ref "C32") (pin "2") (pinfunction "2_2") (pintype "passive"))
      (node (ref "C33") (pin "2") (pinfunction "2_2") (pintype "passive"))
      (node (ref "C34") (pin "2") (pinfunction "2_2") (pintype "passive"))
      (node (ref "C35") (pin "2") (pinfunction "2_2") (pintype "passive"))
      (node (ref "C36") (pin "2") (pinfunction "2_2") (pintype "passive"))
      (node (ref "C37") (pin "-") (pinfunction "-_-") (pintype "passive"))
      (node (ref "C38") (pin "-") (pinfunction "-_-") (pintype "passive"))
      (node (ref "C4") (pin "-") (pinfunction "-_-") (pintype "passive"))
      (node (ref "C5") (pin "-") (pinfunction "-_-") (pintype "passive"))
      (node (ref "C6") (pin "2") (pinfunction "2_2") (pintype "passive"))
      (node (ref "C7") (pin "2") (pinfunction "2_2") (pintype "passive"))
      (node (ref "C8") (pin "2") (pinfunction "2_2") (pintype "passive"))
      (node (ref "C9") (pin "2") (pinfunction "2_2") (pintype "passive"))
      (node (ref "IC1") (pin "1") (pinfunction "ADJ_1") (pintype "input"))
      (node (ref "IC2") (pin "1") (pinfunction "ADJ_1") (pintype "input"))
      (node (ref "JP1") (pin "1") (pinfunction "1_1") (pintype "passive"))
      (node (ref "JP2") (pin "1") (pinfunction "1_1") (pintype "passive"))
      (node (ref "LCD1") (pin "K") (pinfunction "K_K") (pintype "bidirectional"))
      (node (ref "LCD1") (pin "RW") (pinfunction "RW_RW") (pintype "bidirectional"))
      (node (ref "LCD1") (pin "VSS") (pinfunction "VSS_VSS") (pintype "bidirectional"))
      (node (ref "LJOY") (pin "CON") (pinfunction "CON_CON") (pintype "bidirectional"))
      (node (ref "LJOY") (pin "GND") (pinfunction "GND_GND") (pintype "bidirectional"))
      (node (ref "MPU1") (pin "GND") (pinfunction "GND_GND") (pintype "bidirectional"))
      (node (ref "NRF1") (pin "1") (pinfunction "GND_1") (pintype "power_in"))
      (node (ref "R16") (pin "A") (pinfunction "A_A") (pintype "passive"))
      (node (ref "RJOY") (pin "CON") (pinfunction "CON_CON") (pintype "bidirectional"))
      (node (ref "RJOY") (pin "GND") (pinfunction "GND_GND") (pintype "bidirectional"))
      (node (ref "S1") (pin "3") (pinfunction "P_3") (pintype "passive"))
      (node (ref "S1") (pin "4") (pinfunction "P1_4") (pintype "passive"))
      (node (ref "S2") (pin "3") (pinfunction "P_3") (pintype "passive"))
      (node (ref "S2") (pin "4") (pinfunction "P1_4") (pintype "passive"))
      (node (ref "S3") (pin "3") (pinfunction "P_3") (pintype "passive"))
      (node (ref "S3") (pin "4") (pinfunction "P1_4") (pintype "passive"))
      (node (ref "S4") (pin "3") (pinfunction "P_3") (pintype "passive"))
      (node (ref "S4") (pin "4") (pinfunction "P1_4") (pintype "passive"))
      (node (ref "S5") (pin "3") (pinfunction "P_3") (pintype "passive"))
      (node (ref "S5") (pin "4") (pinfunction "P1_4") (pintype "passive"))
      (node (ref "S6") (pin "3") (pinfunction "P_3") (pintype "passive"))
      (node (ref "S6") (pin "4") (pinfunction "P1_4") (pintype "passive"))
      (node (ref "X1") (pin "1") (pinfunction "1_1") (pintype "bidirectional"))
      (node (ref "X2") (pin "2") (pinfunction "2_2") (pintype "bidirectional"))
      (node (ref "X3") (pin "2") (pinfunction "2_2") (pintype "bidirectional"))
      (node (ref "X3") (pin "4") (pinfunction "4_4") (pintype "bidirectional"))
      (node (ref "X4") (pin "2") (pinfunction "2_2") (pintype "bidirectional"))
    )
    (net (code "52") (name "Net-(B1-5V-Pad5V@0)") (class "Default")
      (node (ref "B1") (pin "5V@0") (pinfunction "5V_5V@0") (pintype "bidirectional"))
      (node (ref "C1") (pin "+") (pinfunction "+_+") (pintype "passive"))
      (node (ref "C2") (pin "1") (pinfunction "1_1") (pintype "passive"))
    )
    (net (code "53") (name "Net-(C31-Pad1)") (class "Default")
      (node (ref "C31") (pin "1") (pinfunction "1_1") (pintype "passive"))
      (node (ref "LCD1") (pin "VO") (pinfunction "VO_VO") (pintype "bidirectional"))
      (node (ref "R16") (pin "S") (pinfunction "S_S") (pintype "passive"))
    )
    (net (code "54") (name "Net-(D1-PadA)") (class "Default")
      (node (ref "D1") (pin "A") (pinfunction "A_A") (pintype "passive"))
      (node (ref "JP1") (pin "2") (pinfunction "2_2") (pintype "passive"))
    )
    (net (code "55") (name "Net-(LCD1-PadA)") (class "Default")
      (node (ref "LCD1") (pin "A") (pinfunction "A_A") (pintype "bidirectional"))
      (node (ref "R18") (pin "2") (pinfunction "2_2") (pintype "passive"))
    )
    (net (code "56") (name "Net-(LED1-PadA)") (class "Default")
      (node (ref "LED1") (pin "A") (pinfunction "A_A") (pintype "passive"))
      (node (ref "R22") (pin "2") (pinfunction "2_2") (pintype "passive"))
    )
    (net (code "57") (name "Net-(LED2-PadA)") (class "Default")
      (node (ref "LED2") (pin "A") (pinfunction "A_A") (pintype "passive"))
      (node (ref "R23") (pin "2") (pinfunction "2_2") (pintype "passive"))
    )
    (net (code "58") (name "Net-(LED3-PadA)") (class "Default")
      (node (ref "LED3") (pin "A") (pinfunction "A_A") (pintype "passive"))
      (node (ref "R24") (pin "2") (pinfunction "2_2") (pintype "passive"))
    )
    (net (code "59") (name "Net-(LED4-PadA)") (class "Default")
      (node (ref "LED4") (pin "A") (pinfunction "A_A") (pintype "passive"))
      (node (ref "R25") (pin "2") (pinfunction "2_2") (pintype "passive"))
    )
    (net (code "60") (name "Net-(LED5-PadA)") (class "Default")
      (node (ref "LED5") (pin "A") (pinfunction "A_A") (pintype "passive"))
      (node (ref "R26") (pin "2") (pinfunction "2_2") (pintype "passive"))
    )
    (net (code "61") (name "Net-(LED6-PadA)") (class "Default")
      (node (ref "LED6") (pin "A") (pinfunction "A_A") (pintype "passive"))
      (node (ref "R27") (pin "2") (pinfunction "2_2") (pintype "passive"))
    )
    (net (code "62") (name "V+") (class "Default")
      (node (ref "B1") (pin "VIN") (pinfunction "VIN_VIN") (pintype "bidirectional"))
      (node (ref "C28") (pin "+") (pinfunction "+_+") (pintype "passive"))
      (node (ref "C3") (pin "+") (pinfunction "+_+") (pintype "passive"))
      (node (ref "C37") (pin "+") (pinfunction "+_+") (pintype "passive"))
      (node (ref "C4") (pin "+") (pinfunction "+_+") (pintype "passive"))
      (node (ref "D1") (pin "C") (pinfunction "C_C") (pintype "passive"))
      (node (ref "IC1") (pin "3") (pinfunction "IN_3") (pintype "input"))
      (node (ref "IC2") (pin "3") (pinfunction "IN_3") (pintype "input"))
    )
    (net (code "63") (name "unconnected-(B1-0(RX0)-Pad0)") (class "Default")
      (node (ref "B1") (pin "0") (pinfunction "0(RX0)_0") (pintype "bidirectional"))
    )
    (net (code "64") (name "unconnected-(B1-1(TX0)-Pad1)") (class "Default")
      (node (ref "B1") (pin "1") (pinfunction "1(TX0)_1") (pintype "bidirectional"))
    )
    (net (code "65") (name "unconnected-(B1-5V-Pad5V@1)") (class "Default")
      (node (ref "B1") (pin "5V@1") (pinfunction "5V_5V@1") (pintype "bidirectional"))
    )
    (net (code "66") (name "unconnected-(B1-5V-Pad5V@2)") (class "Default")
      (node (ref "B1") (pin "5V@2") (pinfunction "5V_5V@2") (pintype "bidirectional"))
    )
    (net (code "67") (name "unconnected-(B1-A0(RX0)-PadA0)") (class "Default")
      (node (ref "B1") (pin "A0") (pinfunction "A0(RX0)_A0") (pintype "bidirectional"))
    )
    (net (code "68") (name "unconnected-(B1-A1(TX0)-PadA1)") (class "Default")
      (node (ref "B1") (pin "A1") (pinfunction "A1(TX0)_A1") (pintype "bidirectional"))
    )
    (net (code "69") (name "unconnected-(B1-Pad3.3V)") (class "Default")
      (node (ref "B1") (pin "3.3V") (pinfunction "3.3V_3.3V") (pintype "bidirectional"))
    )
    (net (code "70") (name "unconnected-(B1-Pad31)") (class "Default")
      (node (ref "B1") (pin "31") (pinfunction "31_31") (pintype "bidirectional"))
    )
    (net (code "71") (name "unconnected-(B1-Pad32)") (class "Default")
      (node (ref "B1") (pin "32") (pinfunction "32_32") (pintype "bidirectional"))
    )
    (net (code "72") (name "unconnected-(B1-Pad33)") (class "Default")
      (node (ref "B1") (pin "33") (pinfunction "33_33") (pintype "bidirectional"))
    )
    (net (code "73") (name "unconnected-(B1-Pad34)") (class "Default")
      (node (ref "B1") (pin "34") (pinfunction "34_34") (pintype "bidirectional"))
    )
    (net (code "74") (name "unconnected-(B1-Pad35)") (class "Default")
      (node (ref "B1") (pin "35") (pinfunction "35_35") (pintype "bidirectional"))
    )
    (net (code "75") (name "unconnected-(B1-Pad36)") (class "Default")
      (node (ref "B1") (pin "36") (pinfunction "36_36") (pintype "bidirectional"))
    )
    (net (code "76") (name "unconnected-(B1-Pad37)") (class "Default")
      (node (ref "B1") (pin "37") (pinfunction "37_37") (pintype "bidirectional"))
    )
    (net (code "77") (name "unconnected-(B1-Pad38)") (class "Default")
      (node (ref "B1") (pin "38") (pinfunction "38_38") (pintype "bidirectional"))
    )
    (net (code "78") (name "unconnected-(B1-Pad39)") (class "Default")
      (node (ref "B1") (pin "39") (pinfunction "39_39") (pintype "bidirectional"))
    )
    (net (code "79") (name "unconnected-(B1-Pad53)") (class "Default")
      (node (ref "B1") (pin "53") (pinfunction "53_53") (pintype "bidirectional"))
    )
    (net (code "80") (name "unconnected-(B1-PadA2)") (class "Default")
      (node (ref "B1") (pin "A2") (pinfunction "A2_A2") (pintype "bidirectional"))
    )
    (net (code "81") (name "unconnected-(B1-PadA3)") (class "Default")
      (node (ref "B1") (pin "A3") (pinfunction "A3_A3") (pintype "bidirectional"))
    )
    (net (code "82") (name "unconnected-(B1-PadA4)") (class "Default")
      (node (ref "B1") (pin "A4") (pinfunction "A4_A4") (pintype "bidirectional"))
    )
    (net (code "83") (name "unconnected-(B1-PadA5)") (class "Default")
      (node (ref "B1") (pin "A5") (pinfunction "A5_A5") (pintype "bidirectional"))
    )
    (net (code "84") (name "unconnected-(B1-PadA6)") (class "Default")
      (node (ref "B1") (pin "A6") (pinfunction "A6_A6") (pintype "bidirectional"))
    )
    (net (code "85") (name "unconnected-(B1-PadA7)") (class "Default")
      (node (ref "B1") (pin "A7") (pinfunction "A7_A7") (pintype "bidirectional"))
    )
    (net (code "86") (name "unconnected-(B1-PadA8)") (class "Default")
      (node (ref "B1") (pin "A8") (pinfunction "A8_A8") (pintype "bidirectional"))
    )
    (net (code "87") (name "unconnected-(B1-PadA9)") (class "Default")
      (node (ref "B1") (pin "A9") (pinfunction "A9_A9") (pintype "bidirectional"))
    )
    (net (code "88") (name "unconnected-(B1-PadA10)") (class "Default")
      (node (ref "B1") (pin "A10") (pinfunction "A10_A10") (pintype "bidirectional"))
    )
    (net (code "89") (name "unconnected-(B1-PadAREF)") (class "Default")
      (node (ref "B1") (pin "AREF") (pinfunction "AREF_AREF") (pintype "bidirectional"))
    )
    (net (code "90") (name "unconnected-(LCD1-PadD0)") (class "Default")
      (node (ref "LCD1") (pin "D0") (pinfunction "D0_D0") (pintype "bidirectional"))
    )
    (net (code "91") (name "unconnected-(LCD1-PadD1)") (class "Default")
      (node (ref "LCD1") (pin "D1") (pinfunction "D1_D1") (pintype "bidirectional"))
    )
    (net (code "92") (name "unconnected-(LCD1-PadD2)") (class "Default")
      (node (ref "LCD1") (pin "D2") (pinfunction "D2_D2") (pintype "bidirectional"))
    )
    (net (code "93") (name "unconnected-(LCD1-PadD3)") (class "Default")
      (node (ref "LCD1") (pin "D3") (pinfunction "D3_D3") (pintype "bidirectional"))
    )
    (net (code "94") (name "unconnected-(MPU1-PadAD0)") (class "Default")
      (node (ref "MPU1") (pin "AD0") (pinfunction "AD0_AD0") (pintype "bidirectional"))
    )
    (net (code "95") (name "unconnected-(MPU1-PadFSYNC)") (class "Default")
      (node (ref "MPU1") (pin "FSYNC") (pinfunction "FSYNC_FSYNC") (pintype "bidirectional"))
    )
    (net (code "96") (name "unconnected-(MPU1-PadNCS)") (class "Default")
      (node (ref "MPU1") (pin "NCS") (pinfunction "NCS_NCS") (pintype "bidirectional"))
    )
    (net (code "97") (name "unconnected-(MPU1-PadXCL)") (class "Default")
      (node (ref "MPU1") (pin "XCL") (pinfunction "XCL_XCL") (pintype "bidirectional"))
    )
    (net (code "98") (name "unconnected-(MPU1-PadXDA)") (class "Default")
      (node (ref "MPU1") (pin "XDA") (pinfunction "XDA_XDA") (pintype "bidirectional"))
    )
    (net (code "99") (name "unconnected-(NRF1-IRQ-Pad8)") (class "Default")
      (node (ref "NRF1") (pin "8") (pinfunction "IRQ_8") (pintype "bidirectional"))
    )
  )
)
